# bdebounce.net
KiCad netlist of a schematic drawn in EAGLE
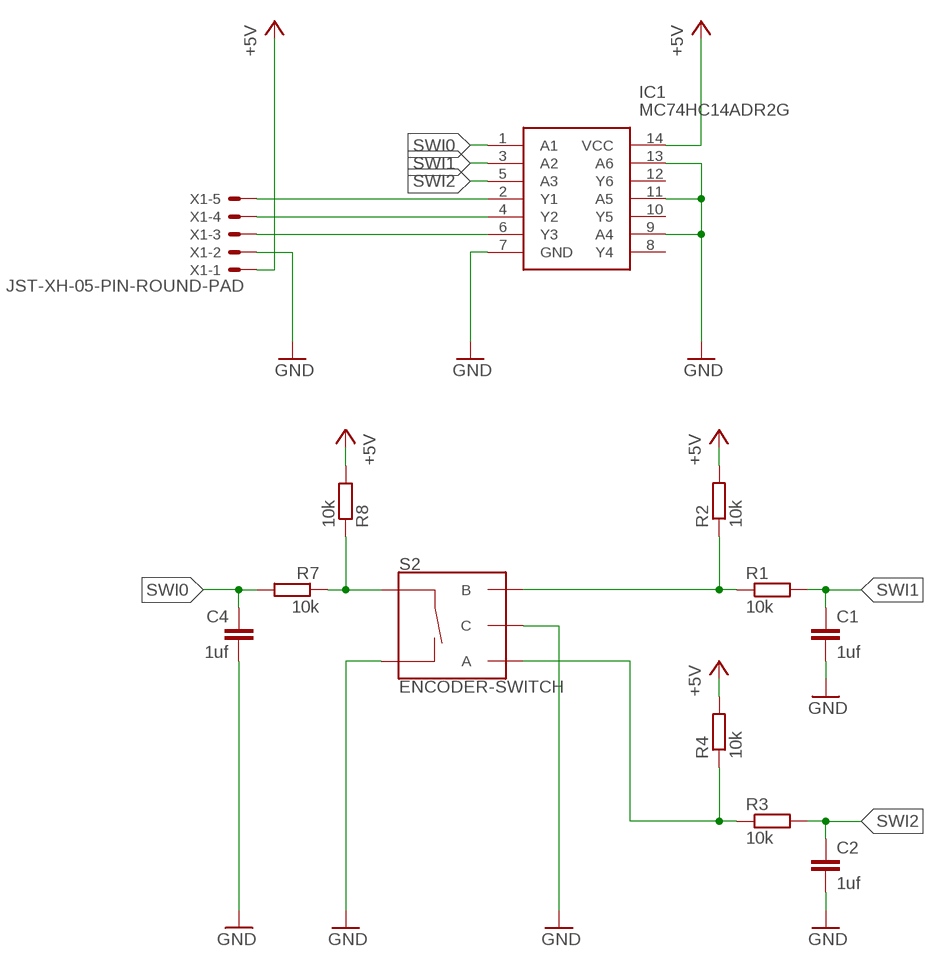
[diagram p0: schematic, sheet 1]

(export (version "E")
  (design (tool "Eeschema 10.0.6"))
  (components
    (comp (ref "C1")
      (value "1uf")
      (footprint "eagle-import:C0805")
      (libsource (lib "eagle-import") (part "C-EUC0805"))
    )
    (comp (ref "C2")
      (value "1uf")
      (footprint "eagle-import:C0805")
      (libsource (lib "eagle-import") (part "C-EUC0805"))
    )
    (comp (ref "C4")
      (value "1uf")
      (footprint "eagle-import:C0805")
      (libsource (lib "eagle-import") (part "C-EUC0805"))
    )
    (comp (ref "IC1")
      (value "MC74HC14ADR2G")
      (footprint "eagle-import:SOIC127P600X175-14N")
      (fields (field (name "MOUSER_PART_NUMBER") "863-MC74HC14ADR2G"))
      (libsource (lib "eagle-import") (part "MC74HC14ADR2G"))
    )
    (comp (ref "R1")
      (value "10k")
      (footprint "eagle-import:R0805")
      (libsource (lib "eagle-import") (part "R-EU_R0805"))
    )
    (comp (ref "R2")
      (value "10k")
      (footprint "eagle-import:R0805")
      (libsource (lib "eagle-import") (part "R-EU_R0805"))
    )
    (comp (ref "R3")
      (value "10k")
      (footprint "eagle-import:R0805")
      (libsource (lib "eagle-import") (part "R-EU_R0805"))
    )
    (comp (ref "R4")
      (value "10k")
      (footprint "eagle-import:R0805")
      (libsource (lib "eagle-import") (part "R-EU_R0805"))
    )
    (comp (ref "R7")
      (value "10k")
      (footprint "eagle-import:R0805")
      (libsource (lib "eagle-import") (part "R-EU_R0805"))
    )
    (comp (ref "R8")
      (value "10k")
      (footprint "eagle-import:R0805")
      (libsource (lib "eagle-import") (part "R-EU_R0805"))
    )
    (comp (ref "S2")
      (value "ENCODER-SWITCH")
      (footprint "eagle-import:ROTARY_ENC_PLAIN")
      (libsource (lib "eagle-import") (part "ENCODER-SWITCH"))
    )
    (comp (ref "X1")
      (value "JST-XH-05-PIN-ROUND-PAD")
      (footprint "eagle-import:JST-XH-05-PACKAGE-ROUND-PAD")
      (libsource (lib "eagle-import") (part "JST-XH-05-PIN-ROUND-PAD"))
    )
  )
  (nets
    (net (code "1") (name "+5V") (class "Default")
      (node (ref "IC1") (pin "14") (pinfunction "VCC_14") (pintype "bidirectional"))
      (node (ref "R2") (pin "2") (pinfunction "2_2") (pintype "passive"))
      (node (ref "R4") (pin "2") (pinfunction "2_2") (pintype "passive"))
      (node (ref "R8") (pin "2") (pinfunction "2_2") (pintype "passive"))
      (node (ref "X1") (pin "1") (pinfunction "S_1") (pintype "passive"))
    )
    (net (code "2") (name "GND") (class "Default")
      (node (ref "C1") (pin "2") (pinfunction "2_2") (pintype "passive"))
      (node (ref "C2") (pin "2") (pinfunction "2_2") (pintype "passive"))
      (node (ref "C4") (pin "2") (pinfunction "2_2") (pintype "passive"))
      (node (ref "IC1") (pin "11") (pinfunction "A5_11") (pintype "bidirectional"))
      (node (ref "IC1") (pin "13") (pinfunction "A6_13") (pintype "bidirectional"))
      (node (ref "IC1") (pin "7") (pinfunction "GND_7") (pintype "bidirectional"))
      (node (ref "IC1") (pin "9") (pinfunction "A4_9") (pintype "bidirectional"))
      (node (ref "S2") (pin "C") (pinfunction "C_C") (pintype "bidirectional"))
      (node (ref "S2") (pin "SW-") (pinfunction "SW-_SW-") (pintype "bidirectional"))
      (node (ref "X1") (pin "2") (pinfunction "S_2") (pintype "passive"))
    )
    (net (code "3") (name "Net-(IC1-Y1)") (class "Default")
      (node (ref "IC1") (pin "2") (pinfunction "Y1_2") (pintype "bidirectional"))
      (node (ref "X1") (pin "5") (pinfunction "S_5") (pintype "passive"))
    )
    (net (code "4") (name "Net-(IC1-Y2)") (class "Default")
      (node (ref "IC1") (pin "4") (pinfunction "Y2_4") (pintype "bidirectional"))
      (node (ref "X1") (pin "4") (pinfunction "S_4") (pintype "passive"))
    )
    (net (code "5") (name "Net-(IC1-Y3)") (class "Default")
      (node (ref "IC1") (pin "6") (pinfunction "Y3_6") (pintype "bidirectional"))
      (node (ref "X1") (pin "3") (pinfunction "S_3") (pintype "passive"))
    )
    (net (code "6") (name "Net-(R1-Pad1)") (class "Default")
      (node (ref "R1") (pin "1") (pinfunction "1_1") (pintype "passive"))
      (node (ref "R2") (pin "1") (pinfunction "1_1") (pintype "passive"))
      (node (ref "S2") (pin "B") (pinfunction "B_B") (pintype "bidirectional"))
    )
    (net (code "7") (name "Net-(R3-Pad1)") (class "Default")
      (node (ref "R3") (pin "1") (pinfunction "1_1") (pintype "passive"))
      (node (ref "R4") (pin "1") (pinfunction "1_1") (pintype "passive"))
      (node (ref "S2") (pin "A") (pinfunction "A_A") (pintype "bidirectional"))
    )
    (net (code "8") (name "Net-(R7-Pad1)") (class "Default")
      (node (ref "R7") (pin "1") (pinfunction "1_1") (pintype "passive"))
      (node (ref "R8") (pin "1") (pinfunction "1_1") (pintype "passive"))
      (node (ref "S2") (pin "SW+") (pinfunction "SW+_SW+") (pintype "bidirectional"))
    )
    (net (code "9") (name "SWI0") (class "Default")
      (node (ref "C4") (pin "1") (pinfunction "1_1") (pintype "passive"))
      (node (ref "IC1") (pin "1") (pinfunction "A1_1") (pintype "bidirectional"))
      (node (ref "R7") (pin "2") (pinfunction "2_2") (pintype "passive"))
    )
    (net (code "10") (name "SWI1") (class "Default")
      (node (ref "C1") (pin "1") (pinfunction "1_1") (pintype "passive"))
      (node (ref "IC1") (pin "3") (pinfunction "A2_3") (pintype "bidirectional"))
      (node (ref "R1") (pin "2") (pinfunction "2_2") (pintype "passive"))
    )
    (net (code "11") (name "SWI2") (class "Default")
      (node (ref "C2") (pin "1") (pinfunction "1_1") (pintype "passive"))
      (node (ref "IC1") (pin "5") (pinfunction "A3_5") (pintype "bidirectional"))
      (node (ref "R3") (pin "2") (pinfunction "2_2") (pintype "passive"))
    )
    (net (code "12") (name "unconnected-(IC1-Y4-Pad8)") (class "Default")
      (node (ref "IC1") (pin "8") (pinfunction "Y4_8") (pintype "bidirectional"))
    )
    (net (code "13") (name "unconnected-(IC1-Y5-Pad10)") (class "Default")
      (node (ref "IC1") (pin "10") (pinfunction "Y5_10") (pintype "bidirectional"))
    )
    (net (code "14") (name "unconnected-(IC1-Y6-Pad12)") (class "Default")
      (node (ref "IC1") (pin "12") (pinfunction "Y6_12") (pintype "bidirectional"))
    )
  )
)
